# VIDEO_DAC_THS8134B.net
KiCad netlist of a schematic drawn in Altium Designer
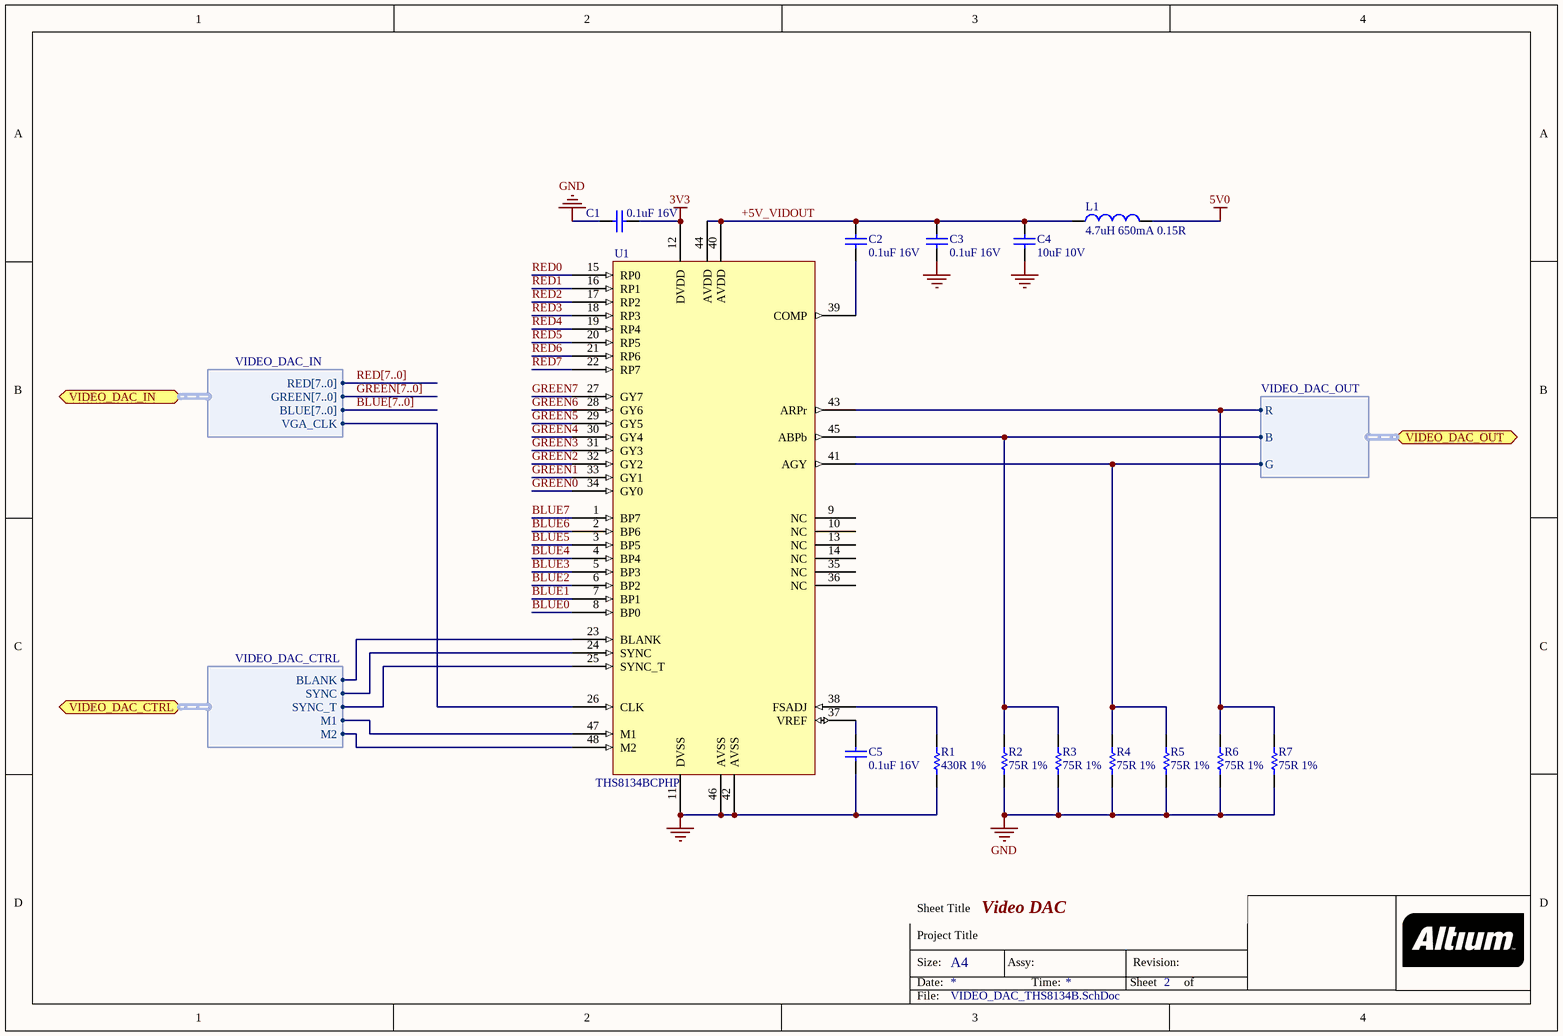
[diagram p0: VIDEO_DAC_THS8134B.SchDoc]

(export (version "E")
  (design (tool "Eeschema 10.0.6"))
  (components
    (comp (ref "C1")
      (value "0.1uF 16V")
      (footprint "CAPC1005-STAR")
      (description "Capacitor, Ceramic, 0.1uF 10% 16V 0402 (1005) X7R")
      (fields (field (name "TOLERANCE") "10 %"))
      (libsource (lib "") (part "CAP-NP_1"))
    )
    (comp (ref "C2")
      (value "0.1uF 16V")
      (footprint "CAPC1005-STAR")
      (description "Capacitor, Ceramic, 0.1uF 10% 16V 0402 (1005) X7R")
      (fields (field (name "TOLERANCE") "10 %"))
      (libsource (lib "AltiumDesignLibrary") (part "CAP-NP"))
    )
    (comp (ref "C3")
      (value "0.1uF 16V")
      (footprint "CAPC1005-STAR")
      (description "Capacitor, Ceramic, 0.1uF 10% 16V 0402 (1005) X7R")
      (fields (field (name "TOLERANCE") "10 %"))
      (libsource (lib "AltiumDesignLibrary") (part "CAP-NP"))
    )
    (comp (ref "C4")
      (value "10uF 10V")
      (footprint "CAPC2012-STAR")
      (description "Capacitor, Ceramic, 10uF 10% 10V 0805 (2012) X5R")
      (fields (field (name "TOLERANCE") "10 %"))
      (libsource (lib "AltiumDesignLibrary") (part "CAP-NP"))
    )
    (comp (ref "C5")
      (value "0.1uF 16V")
      (footprint "CAPC1005-STAR")
      (description "Capacitor, Ceramic, 0.1uF 10% 16V 0402 (1005) X7R")
      (fields (field (name "TOLERANCE") "10 %"))
      (libsource (lib "AltiumDesignLibrary") (part "CAP-NP"))
    )
    (comp (ref "L1")
      (value "4.7uH 650mA 0.15R")
      (footprint "INDC3225")
      (description "Inductor, 4.7uH 650mA 0.15R 1210 (3225) LQH32CN4R7M11L")
      (libsource (lib "AltiumDesignLibrary") (part "IND"))
    )
    (comp (ref "R1")
      (value "430R 1%")
      (footprint "RESC1005-STAR")
      (description "Resistor, 430R 1% 0402 (1005)")
      (fields (field (name "TOLERANCE") "1 %"))
      (libsource (lib "AltiumDesignLibrary") (part "RES"))
    )
    (comp (ref "R2")
      (value "75R 1%")
      (footprint "RESC1005-STAR")
      (description "Resistor, 75R 1% 0402")
      (fields (field (name "TOLERANCE") "1 %"))
      (libsource (lib "AltiumDesignLibrary") (part "RES"))
    )
    (comp (ref "R3")
      (value "75R 1%")
      (footprint "RESC1005-STAR")
      (description "Resistor, 75R 1% 0402")
      (fields (field (name "TOLERANCE") "1 %"))
      (libsource (lib "AltiumDesignLibrary") (part "RES"))
    )
    (comp (ref "R4")
      (value "75R 1%")
      (footprint "RESC1005-STAR")
      (description "Resistor, 75R 1% 0402")
      (fields (field (name "TOLERANCE") "1 %"))
      (libsource (lib "AltiumDesignLibrary") (part "RES"))
    )
    (comp (ref "R5")
      (value "75R 1%")
      (footprint "RESC1005-STAR")
      (description "Resistor, 75R 1% 0402")
      (fields (field (name "TOLERANCE") "1 %"))
      (libsource (lib "AltiumDesignLibrary") (part "RES"))
    )
    (comp (ref "R6")
      (value "75R 1%")
      (footprint "RESC1005-STAR")
      (description "Resistor, 75R 1% 0402")
      (fields (field (name "TOLERANCE") "1 %"))
      (libsource (lib "AltiumDesignLibrary") (part "RES"))
    )
    (comp (ref "R7")
      (value "75R 1%")
      (footprint "RESC1005-STAR")
      (description "Resistor, 75R 1% 0402")
      (fields (field (name "TOLERANCE") "1 %"))
      (libsource (lib "AltiumDesignLibrary") (part "RES"))
    )
    (comp (ref "U1")
      (value "THS8134BCPHP")
      (footprint "TSQFP50P900X900_HS-48")
      (description "THS8134BCPHP, Triple 8-Bit, 80 MSPS Video DAC with Tri-Level Sync Generation")
      (libsource (lib "AltiumDesignLibrary") (part "THS8134"))
    )
  )
  (nets
    (net (code "4") (name "/+5V_VIDOUT") (class "Default")
      (node (ref "C2") (pin "1") (pinfunction "1_1") (pintype "passive"))
      (node (ref "C3") (pin "1") (pinfunction "1_1") (pintype "passive"))
      (node (ref "C4") (pin "2") (pinfunction "2_2") (pintype "passive"))
      (node (ref "L1") (pin "2") (pinfunction "2_2") (pintype "passive"))
      (node (ref "U1") (pin "40") (pinfunction "AVDD_40") (pintype "power_in"))
      (node (ref "U1") (pin "44") (pinfunction "AVDD_44") (pintype "power_in"))
    )
    (net (code "5") (name "/B") (class "Default")
      (node (ref "R2") (pin "1") (pinfunction "1_1") (pintype "passive"))
      (node (ref "R3") (pin "2") (pinfunction "2_2") (pintype "passive"))
      (node (ref "U1") (pin "45") (pinfunction "ABPb_45") (pintype "output"))
    )
    (net (code "6") (name "/BLANK") (class "Default")
      (node (ref "U1") (pin "23") (pinfunction "BLANK_23") (pintype "input"))
    )
    (net (code "7") (name "/BLUE0") (class "Default")
      (node (ref "U1") (pin "8") (pinfunction "BP0_8") (pintype "input"))
    )
    (net (code "8") (name "/BLUE1") (class "Default")
      (node (ref "U1") (pin "7") (pinfunction "BP1_7") (pintype "input"))
    )
    (net (code "9") (name "/BLUE2") (class "Default")
      (node (ref "U1") (pin "6") (pinfunction "BP2_6") (pintype "input"))
    )
    (net (code "10") (name "/BLUE3") (class "Default")
      (node (ref "U1") (pin "5") (pinfunction "BP3_5") (pintype "input"))
    )
    (net (code "11") (name "/BLUE4") (class "Default")
      (node (ref "U1") (pin "4") (pinfunction "BP4_4") (pintype "input"))
    )
    (net (code "12") (name "/BLUE5") (class "Default")
      (node (ref "U1") (pin "3") (pinfunction "BP5_3") (pintype "input"))
    )
    (net (code "13") (name "/BLUE6") (class "Default")
      (node (ref "U1") (pin "2") (pinfunction "BP6_2") (pintype "input"))
    )
    (net (code "14") (name "/BLUE7") (class "Default")
      (node (ref "U1") (pin "1") (pinfunction "BP7_1") (pintype "input"))
    )
    (net (code "16") (name "/G") (class "Default")
      (node (ref "R4") (pin "1") (pinfunction "1_1") (pintype "passive"))
      (node (ref "R5") (pin "2") (pinfunction "2_2") (pintype "passive"))
      (node (ref "U1") (pin "41") (pinfunction "AGY_41") (pintype "output"))
    )
    (net (code "17") (name "/GREEN0") (class "Default")
      (node (ref "U1") (pin "34") (pinfunction "GY0_34") (pintype "input"))
    )
    (net (code "18") (name "/GREEN1") (class "Default")
      (node (ref "U1") (pin "33") (pinfunction "GY1_33") (pintype "input"))
    )
    (net (code "19") (name "/GREEN2") (class "Default")
      (node (ref "U1") (pin "32") (pinfunction "GY2_32") (pintype "input"))
    )
    (net (code "20") (name "/GREEN3") (class "Default")
      (node (ref "U1") (pin "31") (pinfunction "GY3_31") (pintype "input"))
    )
    (net (code "21") (name "/GREEN4") (class "Default")
      (node (ref "U1") (pin "30") (pinfunction "GY4_30") (pintype "input"))
    )
    (net (code "22") (name "/GREEN5") (class "Default")
      (node (ref "U1") (pin "29") (pinfunction "GY5_29") (pintype "input"))
    )
    (net (code "23") (name "/GREEN6") (class "Default")
      (node (ref "U1") (pin "28") (pinfunction "GY6_28") (pintype "input"))
    )
    (net (code "24") (name "/GREEN7") (class "Default")
      (node (ref "U1") (pin "27") (pinfunction "GY7_27") (pintype "input"))
    )
    (net (code "26") (name "/M1") (class "Default")
      (node (ref "U1") (pin "47") (pinfunction "M1_47") (pintype "input"))
    )
    (net (code "27") (name "/M2") (class "Default")
      (node (ref "U1") (pin "48") (pinfunction "M2_48") (pintype "input"))
    )
    (net (code "28") (name "/R") (class "Default")
      (node (ref "R6") (pin "2") (pinfunction "2_2") (pintype "passive"))
      (node (ref "R7") (pin "2") (pinfunction "2_2") (pintype "passive"))
      (node (ref "U1") (pin "43") (pinfunction "ARPr_43") (pintype "output"))
    )
    (net (code "29") (name "/RED0") (class "Default")
      (node (ref "U1") (pin "15") (pinfunction "RP0_15") (pintype "input"))
    )
    (net (code "30") (name "/RED1") (class "Default")
      (node (ref "U1") (pin "16") (pinfunction "RP1_16") (pintype "input"))
    )
    (net (code "31") (name "/RED2") (class "Default")
      (node (ref "U1") (pin "17") (pinfunction "RP2_17") (pintype "input"))
    )
    (net (code "32") (name "/RED3") (class "Default")
      (node (ref "U1") (pin "18") (pinfunction "RP3_18") (pintype "input"))
    )
    (net (code "33") (name "/RED4") (class "Default")
      (node (ref "U1") (pin "19") (pinfunction "RP4_19") (pintype "input"))
    )
    (net (code "34") (name "/RED5") (class "Default")
      (node (ref "U1") (pin "20") (pinfunction "RP5_20") (pintype "input"))
    )
    (net (code "35") (name "/RED6") (class "Default")
      (node (ref "U1") (pin "21") (pinfunction "RP6_21") (pintype "input"))
    )
    (net (code "36") (name "/RED7") (class "Default")
      (node (ref "U1") (pin "22") (pinfunction "RP7_22") (pintype "input"))
    )
    (net (code "38") (name "/SYNC") (class "Default")
      (node (ref "U1") (pin "24") (pinfunction "SYNC_24") (pintype "input"))
    )
    (net (code "39") (name "/SYNC_T") (class "Default")
      (node (ref "U1") (pin "25") (pinfunction "SYNC_T_25") (pintype "input"))
    )
    (net (code "40") (name "/VGA_CLK") (class "Default")
      (node (ref "U1") (pin "26") (pinfunction "CLK_26") (pintype "input"))
    )
    (net (code "44") (name "3V3") (class "Default")
      (node (ref "C1") (pin "1") (pinfunction "1_1") (pintype "passive"))
      (node (ref "U1") (pin "12") (pinfunction "DVDD_12") (pintype "power_in"))
    )
    (net (code "45") (name "5V0") (class "Default")
      (node (ref "L1") (pin "1") (pinfunction "1_1") (pintype "passive"))
    )
    (net (code "46") (name "GND") (class "Default")
      (node (ref "C1") (pin "2") (pinfunction "2_2") (pintype "passive"))
      (node (ref "C3") (pin "2") (pinfunction "2_2") (pintype "passive"))
      (node (ref "C4") (pin "1") (pinfunction "1_1") (pintype "passive"))
      (node (ref "C5") (pin "2") (pinfunction "2_2") (pintype "passive"))
      (node (ref "R1") (pin "1") (pinfunction "1_1") (pintype "passive"))
      (node (ref "R2") (pin "2") (pinfunction "2_2") (pintype "passive"))
      (node (ref "R3") (pin "1") (pinfunction "1_1") (pintype "passive"))
      (node (ref "R4") (pin "2") (pinfunction "2_2") (pintype "passive"))
      (node (ref "R5") (pin "1") (pinfunction "1_1") (pintype "passive"))
      (node (ref "R6") (pin "1") (pinfunction "1_1") (pintype "passive"))
      (node (ref "R7") (pin "1") (pinfunction "1_1") (pintype "passive"))
      (node (ref "U1") (pin "11") (pinfunction "DVSS_11") (pintype "power_in"))
      (node (ref "U1") (pin "42") (pinfunction "AVSS_42") (pintype "power_in"))
      (node (ref "U1") (pin "46") (pinfunction "AVSS_46") (pintype "power_in"))
    )
    (net (code "47") (name "Net-(U1-COMP)") (class "Default")
      (node (ref "C2") (pin "2") (pinfunction "2_2") (pintype "passive"))
      (node (ref "U1") (pin "39") (pinfunction "COMP_39") (pintype "output"))
    )
    (net (code "48") (name "Net-(U1-FSADJ)") (class "Default")
      (node (ref "R1") (pin "2") (pinfunction "2_2") (pintype "passive"))
      (node (ref "U1") (pin "38") (pinfunction "FSADJ_38") (pintype "input"))
    )
    (net (code "49") (name "Net-(U1-VREF)") (class "Default")
      (node (ref "C5") (pin "1") (pinfunction "1_1") (pintype "passive"))
      (node (ref "U1") (pin "37") (pinfunction "VREF_37") (pintype "bidirectional"))
    )
    (net (code "50") (name "unconnected-(U1-NC-Pad9)") (class "Default")
      (node (ref "U1") (pin "9") (pinfunction "NC_9") (pintype "passive"))
    )
    (net (code "51") (name "unconnected-(U1-NC-Pad10)") (class "Default")
      (node (ref "U1") (pin "10") (pinfunction "NC_10") (pintype "passive"))
    )
    (net (code "52") (name "unconnected-(U1-NC-Pad13)") (class "Default")
      (node (ref "U1") (pin "13") (pinfunction "NC_13") (pintype "passive"))
    )
    (net (code "53") (name "unconnected-(U1-NC-Pad14)") (class "Default")
      (node (ref "U1") (pin "14") (pinfunction "NC_14") (pintype "passive"))
    )
    (net (code "54") (name "unconnected-(U1-NC-Pad35)") (class "Default")
      (node (ref "U1") (pin "35") (pinfunction "NC_35") (pintype "passive"))
    )
    (net (code "55") (name "unconnected-(U1-NC-Pad36)") (class "Default")
      (node (ref "U1") (pin "36") (pinfunction "NC_36") (pintype "passive"))
    )
  )
)
